# SoftRoboticsToolKit.net
KiCad netlist of a schematic drawn in Altium Designer
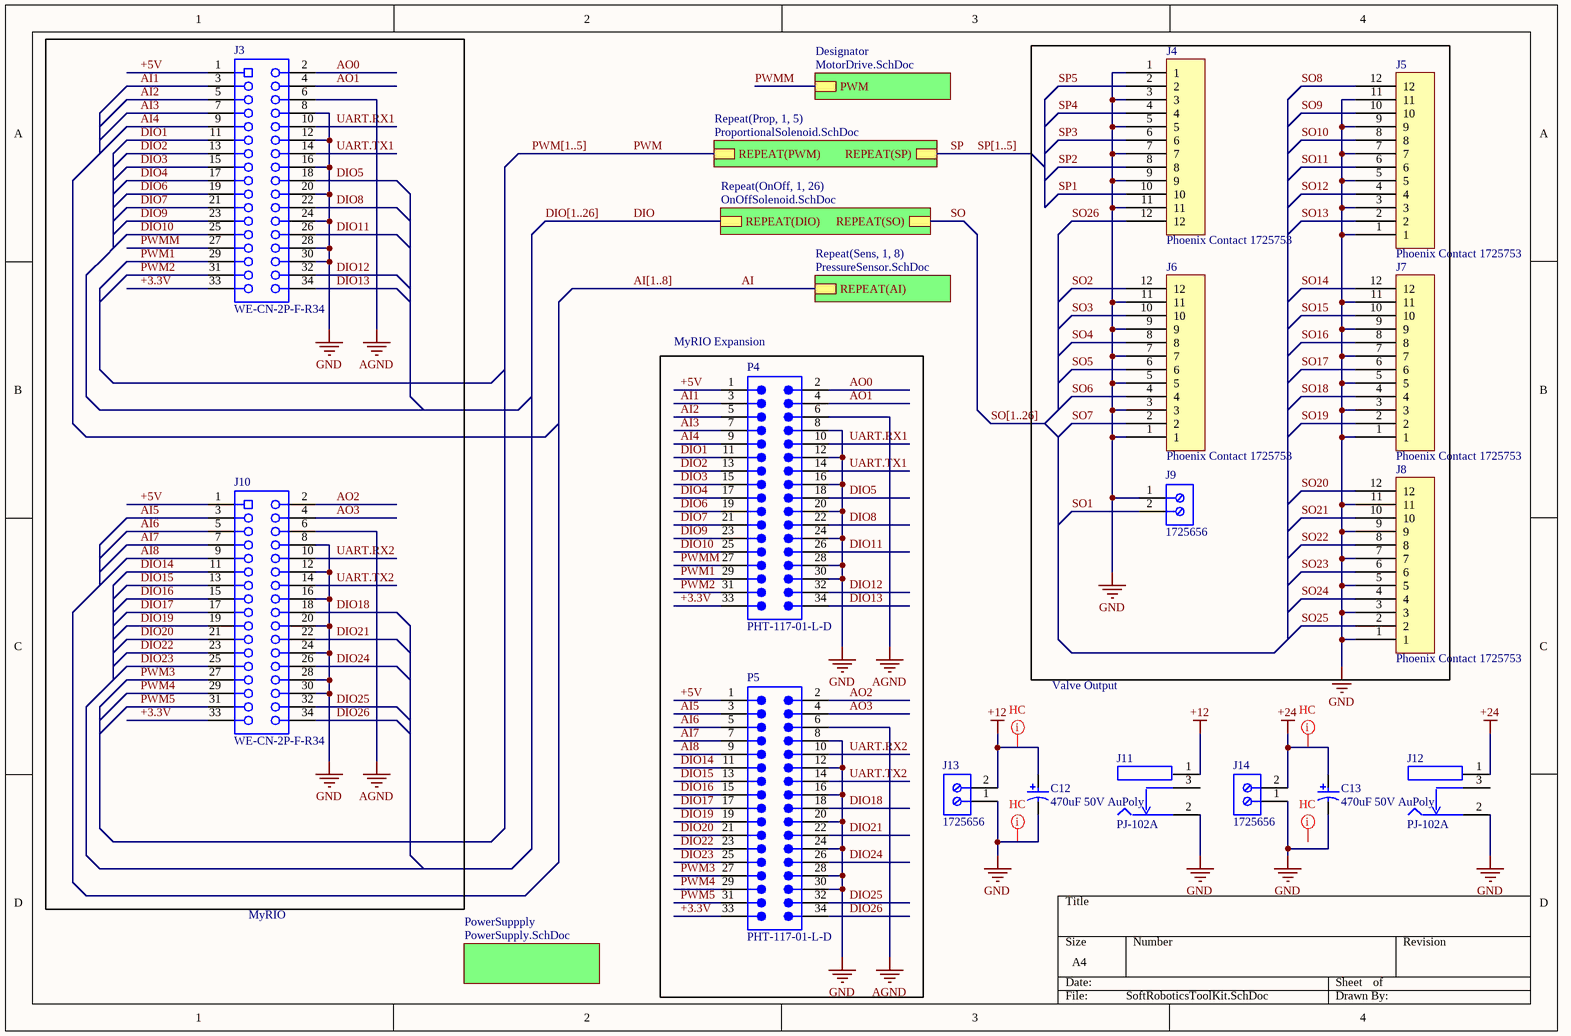
[diagram p0: SoftRoboticsToolKit.SchDoc]

(export (version "E")
  (design (tool "Eeschema 10.0.6"))
  (components
    (comp (ref "C12")
      (value "470uF 50V AuPoly")
      (footprint "CAPAE137130X163M")
      (fields (field (name "VOLTAGE") "25VDC") (field (name "MANUFACTURER") "AVX"))
      (libsource (lib "Schlib1") (part "C-Poly"))
    )
    (comp (ref "C13")
      (value "470uF 50V AuPoly")
      (footprint "CAPAE137130X163M")
      (fields (field (name "VOLTAGE") "25VDC") (field (name "MANUFACTURER") "AVX"))
      (libsource (lib "Schlib1") (part "C-Poly"))
    )
    (comp (ref "J3")
      (value "WE-CN-2P-F-R34")
      (footprint "613034243121")
      (libsource (lib "Schlib1") (part "WE-CN-2P-F-R34"))
    )
    (comp (ref "J4")
      (value "Phoenix Contact 1725753")
      (footprint "PHOE-1725656-12")
      (libsource (lib "") (part "1725753_1"))
    )
    (comp (ref "J5")
      (value "Phoenix Contact 1725753")
      (footprint "PHOE-1725656-12")
      (libsource (lib "Schlib1") (part "1725753"))
    )
    (comp (ref "J6")
      (value "Phoenix Contact 1725753")
      (footprint "PHOE-1725656-12")
      (libsource (lib "Schlib1") (part "1725753"))
    )
    (comp (ref "J7")
      (value "Phoenix Contact 1725753")
      (footprint "PHOE-1725656-12")
      (libsource (lib "Schlib1") (part "1725753"))
    )
    (comp (ref "J8")
      (value "Phoenix Contact 1725753")
      (footprint "PHOE-1725656-12")
      (libsource (lib "Schlib1") (part "1725753"))
    )
    (comp (ref "J9")
      (value "1725656")
      (footprint "PHOE-1725656-2")
      (description "Male Header, Pitch 2.54 mm, 1 x 2 Position, Height 9 mm, Tail Length 3.5 mm")
      (fields (field (name "MANUFACTURER") "Phoenix Contact"))
      (libsource (lib "Altium Content Vault") (part "CN-1P-F-TB2"))
    )
    (comp (ref "J10")
      (value "WE-CN-2P-F-R34")
      (footprint "613034243121")
      (libsource (lib "Schlib1") (part "WE-CN-2P-F-R34"))
    )
    (comp (ref "J11")
      (value "PJ-102A")
      (footprint "FP-PJ-102A-MFG")
      (description "CONN PWR JACK 2X5.5MM SOLDER")
      (fields (field (name "MANUFACTURER") "CUI") (field (name "VOLTAGE") "24V"))
      (libsource (lib "Altium Content Vault") (part "0685d7ee7311ef3291d1b1b03391b7d"))
    )
    (comp (ref "J12")
      (value "PJ-102A")
      (footprint "FP-PJ-102A-MFG")
      (description "CONN PWR JACK 2X5.5MM SOLDER")
      (fields (field (name "MANUFACTURER") "CUI") (field (name "VOLTAGE") "24V"))
      (libsource (lib "Altium Content Vault") (part "0685d7ee7311ef3291d1b1b03391b7d"))
    )
    (comp (ref "J13")
      (value "1725656")
      (footprint "PHOE-1725656-2")
      (description "Male Header, Pitch 2.54 mm, 1 x 2 Position, Height 9 mm, Tail Length 3.5 mm")
      (fields (field (name "MANUFACTURER") "Phoenix Contact"))
      (libsource (lib "Altium Content Vault") (part "CN-1P-F-TB2"))
    )
    (comp (ref "J14")
      (value "1725656")
      (footprint "PHOE-1725656-2")
      (description "Male Header, Pitch 2.54 mm, 1 x 2 Position, Height 9 mm, Tail Length 3.5 mm")
      (fields (field (name "MANUFACTURER") "Phoenix Contact"))
      (libsource (lib "Altium Content Vault") (part "CN-1P-F-TB2"))
    )
    (comp (ref "P4")
      (value "PHT-117-01-L-D")
      (footprint "PHT-117-01-L-D")
      (libsource (lib "Schlib1") (part "PHT-117-01-L-D"))
    )
    (comp (ref "P5")
      (value "PHT-117-01-L-D")
      (footprint "PHT-117-01-L-D")
      (libsource (lib "Schlib1") (part "PHT-117-01-L-D"))
    )
  )
  (nets
    (net (code "1") (name "+12") (class "Default")
      (node (ref "C12") (pin "1") (pinfunction "1_1") (pintype "passive"))
      (node (ref "J11") (pin "1") (pinfunction "1_1") (pintype "passive"))
      (node (ref "J13") (pin "2") (pinfunction "2_2") (pintype "passive"))
    )
    (net (code "2") (name "+24") (class "Default")
      (node (ref "C13") (pin "1") (pinfunction "1_1") (pintype "passive"))
      (node (ref "J12") (pin "1") (pinfunction "1_1") (pintype "passive"))
      (node (ref "J14") (pin "2") (pinfunction "2_2") (pintype "passive"))
    )
    (net (code "3") (name "/+3.3V") (class "Default")
      (node (ref "J10") (pin "33") (pinfunction "33_33") (pintype "passive"))
      (node (ref "J3") (pin "33") (pinfunction "33_33") (pintype "passive"))
      (node (ref "P4") (pin "33") (pinfunction "33_33") (pintype "passive"))
      (node (ref "P5") (pin "33") (pinfunction "33_33") (pintype "passive"))
    )
    (net (code "4") (name "/+5V") (class "Default")
      (node (ref "J10") (pin "1") (pinfunction "1_1") (pintype "passive"))
      (node (ref "J3") (pin "1") (pinfunction "1_1") (pintype "passive"))
      (node (ref "P4") (pin "1") (pinfunction "1_1") (pintype "passive"))
      (node (ref "P5") (pin "1") (pinfunction "1_1") (pintype "passive"))
    )
    (net (code "6") (name "/AI1") (class "Default")
      (node (ref "J3") (pin "3") (pinfunction "3_3") (pintype "passive"))
      (node (ref "P4") (pin "3") (pinfunction "3_3") (pintype "passive"))
    )
    (net (code "7") (name "/AI2") (class "Default")
      (node (ref "J3") (pin "5") (pinfunction "5_5") (pintype "passive"))
      (node (ref "P4") (pin "5") (pinfunction "5_5") (pintype "passive"))
    )
    (net (code "8") (name "/AI3") (class "Default")
      (node (ref "J3") (pin "7") (pinfunction "7_7") (pintype "passive"))
      (node (ref "P4") (pin "7") (pinfunction "7_7") (pintype "passive"))
    )
    (net (code "9") (name "/AI4") (class "Default")
      (node (ref "J3") (pin "9") (pinfunction "9_9") (pintype "passive"))
      (node (ref "P4") (pin "9") (pinfunction "9_9") (pintype "passive"))
    )
    (net (code "10") (name "/AI5") (class "Default")
      (node (ref "J10") (pin "3") (pinfunction "3_3") (pintype "passive"))
      (node (ref "P5") (pin "3") (pinfunction "3_3") (pintype "passive"))
    )
    (net (code "11") (name "/AI6") (class "Default")
      (node (ref "J10") (pin "5") (pinfunction "5_5") (pintype "passive"))
      (node (ref "P5") (pin "5") (pinfunction "5_5") (pintype "passive"))
    )
    (net (code "12") (name "/AI7") (class "Default")
      (node (ref "J10") (pin "7") (pinfunction "7_7") (pintype "passive"))
      (node (ref "P5") (pin "7") (pinfunction "7_7") (pintype "passive"))
    )
    (net (code "13") (name "/AI8") (class "Default")
      (node (ref "J10") (pin "9") (pinfunction "9_9") (pintype "passive"))
      (node (ref "P5") (pin "9") (pinfunction "9_9") (pintype "passive"))
    )
    (net (code "15") (name "/AO0") (class "Default")
      (node (ref "J3") (pin "2") (pinfunction "2_2") (pintype "passive"))
      (node (ref "P4") (pin "2") (pinfunction "2_2") (pintype "passive"))
    )
    (net (code "16") (name "/AO1") (class "Default")
      (node (ref "J3") (pin "4") (pinfunction "4_4") (pintype "passive"))
      (node (ref "P4") (pin "4") (pinfunction "4_4") (pintype "passive"))
    )
    (net (code "17") (name "/AO2") (class "Default")
      (node (ref "J10") (pin "2") (pinfunction "2_2") (pintype "passive"))
      (node (ref "P5") (pin "2") (pinfunction "2_2") (pintype "passive"))
    )
    (net (code "18") (name "/AO3") (class "Default")
      (node (ref "J10") (pin "4") (pinfunction "4_4") (pintype "passive"))
      (node (ref "P5") (pin "4") (pinfunction "4_4") (pintype "passive"))
    )
    (net (code "20") (name "/DIO1") (class "Default")
      (node (ref "J3") (pin "11") (pinfunction "11_11") (pintype "passive"))
      (node (ref "P4") (pin "11") (pinfunction "11_11") (pintype "passive"))
    )
    (net (code "21") (name "/DIO2") (class "Default")
      (node (ref "J3") (pin "13") (pinfunction "13_13") (pintype "passive"))
      (node (ref "P4") (pin "13") (pinfunction "13_13") (pintype "passive"))
    )
    (net (code "22") (name "/DIO3") (class "Default")
      (node (ref "J3") (pin "15") (pinfunction "15_15") (pintype "passive"))
      (node (ref "P4") (pin "15") (pinfunction "15_15") (pintype "passive"))
    )
    (net (code "23") (name "/DIO4") (class "Default")
      (node (ref "J3") (pin "17") (pinfunction "17_17") (pintype "passive"))
      (node (ref "P4") (pin "17") (pinfunction "17_17") (pintype "passive"))
    )
    (net (code "24") (name "/DIO5") (class "Default")
      (node (ref "J3") (pin "18") (pinfunction "18_18") (pintype "passive"))
      (node (ref "P4") (pin "18") (pinfunction "18_18") (pintype "passive"))
    )
    (net (code "25") (name "/DIO6") (class "Default")
      (node (ref "J3") (pin "19") (pinfunction "19_19") (pintype "passive"))
      (node (ref "P4") (pin "19") (pinfunction "19_19") (pintype "passive"))
    )
    (net (code "26") (name "/DIO7") (class "Default")
      (node (ref "J3") (pin "21") (pinfunction "21_21") (pintype "passive"))
      (node (ref "P4") (pin "21") (pinfunction "21_21") (pintype "passive"))
    )
    (net (code "27") (name "/DIO8") (class "Default")
      (node (ref "J3") (pin "22") (pinfunction "22_22") (pintype "passive"))
      (node (ref "P4") (pin "22") (pinfunction "22_22") (pintype "passive"))
    )
    (net (code "28") (name "/DIO9") (class "Default")
      (node (ref "J3") (pin "23") (pinfunction "23_23") (pintype "passive"))
      (node (ref "P4") (pin "23") (pinfunction "23_23") (pintype "passive"))
    )
    (net (code "29") (name "/DIO10") (class "Default")
      (node (ref "J3") (pin "25") (pinfunction "25_25") (pintype "passive"))
      (node (ref "P4") (pin "25") (pinfunction "25_25") (pintype "passive"))
    )
    (net (code "30") (name "/DIO11") (class "Default")
      (node (ref "J3") (pin "26") (pinfunction "26_26") (pintype "passive"))
      (node (ref "P4") (pin "26") (pinfunction "26_26") (pintype "passive"))
    )
    (net (code "31") (name "/DIO12") (class "Default")
      (node (ref "J3") (pin "32") (pinfunction "32_32") (pintype "passive"))
      (node (ref "P4") (pin "32") (pinfunction "32_32") (pintype "passive"))
    )
    (net (code "32") (name "/DIO13") (class "Default")
      (node (ref "J3") (pin "34") (pinfunction "34_34") (pintype "passive"))
      (node (ref "P4") (pin "34") (pinfunction "34_34") (pintype "passive"))
    )
    (net (code "33") (name "/DIO14") (class "Default")
      (node (ref "J10") (pin "11") (pinfunction "11_11") (pintype "passive"))
      (node (ref "P5") (pin "11") (pinfunction "11_11") (pintype "passive"))
    )
    (net (code "34") (name "/DIO15") (class "Default")
      (node (ref "J10") (pin "13") (pinfunction "13_13") (pintype "passive"))
      (node (ref "P5") (pin "13") (pinfunction "13_13") (pintype "passive"))
    )
    (net (code "35") (name "/DIO16") (class "Default")
      (node (ref "J10") (pin "15") (pinfunction "15_15") (pintype "passive"))
      (node (ref "P5") (pin "15") (pinfunction "15_15") (pintype "passive"))
    )
    (net (code "36") (name "/DIO17") (class "Default")
      (node (ref "J10") (pin "17") (pinfunction "17_17") (pintype "passive"))
      (node (ref "P5") (pin "17") (pinfunction "17_17") (pintype "passive"))
    )
    (net (code "37") (name "/DIO18") (class "Default")
      (node (ref "J10") (pin "18") (pinfunction "18_18") (pintype "passive"))
      (node (ref "P5") (pin "18") (pinfunction "18_18") (pintype "passive"))
    )
    (net (code "38") (name "/DIO19") (class "Default")
      (node (ref "J10") (pin "19") (pinfunction "19_19") (pintype "passive"))
      (node (ref "P5") (pin "19") (pinfunction "19_19") (pintype "passive"))
    )
    (net (code "39") (name "/DIO20") (class "Default")
      (node (ref "J10") (pin "21") (pinfunction "21_21") (pintype "passive"))
      (node (ref "P5") (pin "21") (pinfunction "21_21") (pintype "passive"))
    )
    (net (code "40") (name "/DIO21") (class "Default")
      (node (ref "J10") (pin "22") (pinfunction "22_22") (pintype "passive"))
      (node (ref "P5") (pin "22") (pinfunction "22_22") (pintype "passive"))
    )
    (net (code "41") (name "/DIO22") (class "Default")
      (node (ref "J10") (pin "23") (pinfunction "23_23") (pintype "passive"))
      (node (ref "P5") (pin "23") (pinfunction "23_23") (pintype "passive"))
    )
    (net (code "42") (name "/DIO23") (class "Default")
      (node (ref "J10") (pin "25") (pinfunction "25_25") (pintype "passive"))
      (node (ref "P5") (pin "25") (pinfunction "25_25") (pintype "passive"))
    )
    (net (code "43") (name "/DIO24") (class "Default")
      (node (ref "J10") (pin "26") (pinfunction "26_26") (pintype "passive"))
      (node (ref "P5") (pin "26") (pinfunction "26_26") (pintype "passive"))
    )
    (net (code "44") (name "/DIO25") (class "Default")
      (node (ref "J10") (pin "32") (pinfunction "32_32") (pintype "passive"))
      (node (ref "P5") (pin "32") (pinfunction "32_32") (pintype "passive"))
    )
    (net (code "45") (name "/DIO26") (class "Default")
      (node (ref "J10") (pin "34") (pinfunction "34_34") (pintype "passive"))
      (node (ref "P5") (pin "34") (pinfunction "34_34") (pintype "passive"))
    )
    (net (code "48") (name "/PWM1") (class "Default")
      (node (ref "J3") (pin "29") (pinfunction "29_29") (pintype "passive"))
      (node (ref "P4") (pin "29") (pinfunction "29_29") (pintype "passive"))
    )
    (net (code "49") (name "/PWM2") (class "Default")
      (node (ref "J3") (pin "31") (pinfunction "31_31") (pintype "passive"))
      (node (ref "P4") (pin "31") (pinfunction "31_31") (pintype "passive"))
    )
    (net (code "50") (name "/PWM3") (class "Default")
      (node (ref "J10") (pin "27") (pinfunction "27_27") (pintype "passive"))
      (node (ref "P5") (pin "27") (pinfunction "27_27") (pintype "passive"))
    )
    (net (code "51") (name "/PWM4") (class "Default")
      (node (ref "J10") (pin "29") (pinfunction "29_29") (pintype "passive"))
      (node (ref "P5") (pin "29") (pinfunction "29_29") (pintype "passive"))
    )
    (net (code "52") (name "/PWM5") (class "Default")
      (node (ref "J10") (pin "31") (pinfunction "31_31") (pintype "passive"))
      (node (ref "P5") (pin "31") (pinfunction "31_31") (pintype "passive"))
    )
    (net (code "53") (name "/PWMM") (class "Default")
      (node (ref "J3") (pin "27") (pinfunction "27_27") (pintype "passive"))
      (node (ref "P4") (pin "27") (pinfunction "27_27") (pintype "passive"))
    )
    (net (code "56") (name "/SO1") (class "Default")
      (node (ref "J9") (pin "2") (pinfunction "2_2") (pintype "passive"))
    )
    (net (code "57") (name "/SO2") (class "Default")
      (node (ref "J6") (pin "12") (pinfunction "12_12") (pintype "passive"))
    )
    (net (code "58") (name "/SO3") (class "Default")
      (node (ref "J6") (pin "10") (pinfunction "10_10") (pintype "passive"))
    )
    (net (code "59") (name "/SO4") (class "Default")
      (node (ref "J6") (pin "8") (pinfunction "8_8") (pintype "passive"))
    )
    (net (code "60") (name "/SO5") (class "Default")
      (node (ref "J6") (pin "6") (pinfunction "6_6") (pintype "passive"))
    )
    (net (code "61") (name "/SO6") (class "Default")
      (node (ref "J6") (pin "4") (pinfunction "4_4") (pintype "passive"))
    )
    (net (code "62") (name "/SO7") (class "Default")
      (node (ref "J6") (pin "2") (pinfunction "2_2") (pintype "passive"))
    )
    (net (code "63") (name "/SO8") (class "Default")
      (node (ref "J5") (pin "12") (pinfunction "12_12") (pintype "passive"))
    )
    (net (code "64") (name "/SO9") (class "Default")
      (node (ref "J5") (pin "10") (pinfunction "10_10") (pintype "passive"))
    )
    (net (code "65") (name "/SO10") (class "Default")
      (node (ref "J5") (pin "8") (pinfunction "8_8") (pintype "passive"))
    )
    (net (code "66") (name "/SO11") (class "Default")
      (node (ref "J5") (pin "6") (pinfunction "6_6") (pintype "passive"))
    )
    (net (code "67") (name "/SO12") (class "Default")
      (node (ref "J5") (pin "4") (pinfunction "4_4") (pintype "passive"))
    )
    (net (code "68") (name "/SO13") (class "Default")
      (node (ref "J5") (pin "2") (pinfunction "2_2") (pintype "passive"))
    )
    (net (code "69") (name "/SO14") (class "Default")
      (node (ref "J7") (pin "12") (pinfunction "12_12") (pintype "passive"))
    )
    (net (code "70") (name "/SO15") (class "Default")
      (node (ref "J7") (pin "10") (pinfunction "10_10") (pintype "passive"))
    )
    (net (code "71") (name "/SO16") (class "Default")
      (node (ref "J7") (pin "8") (pinfunction "8_8") (pintype "passive"))
    )
    (net (code "72") (name "/SO17") (class "Default")
      (node (ref "J7") (pin "6") (pinfunction "6_6") (pintype "passive"))
    )
    (net (code "73") (name "/SO18") (class "Default")
      (node (ref "J7") (pin "4") (pinfunction "4_4") (pintype "passive"))
    )
    (net (code "74") (name "/SO19") (class "Default")
      (node (ref "J7") (pin "2") (pinfunction "2_2") (pintype "passive"))
    )
    (net (code "75") (name "/SO20") (class "Default")
      (node (ref "J8") (pin "12") (pinfunction "12_12") (pintype "passive"))
    )
    (net (code "76") (name "/SO21") (class "Default")
      (node (ref "J8") (pin "10") (pinfunction "10_10") (pintype "passive"))
    )
    (net (code "77") (name "/SO22") (class "Default")
      (node (ref "J8") (pin "8") (pinfunction "8_8") (pintype "passive"))
    )
    (net (code "78") (name "/SO23") (class "Default")
      (node (ref "J8") (pin "6") (pinfunction "6_6") (pintype "passive"))
    )
    (net (code "79") (name "/SO24") (class "Default")
      (node (ref "J8") (pin "4") (pinfunction "4_4") (pintype "passive"))
    )
    (net (code "80") (name "/SO25") (class "Default")
      (node (ref "J8") (pin "2") (pinfunction "2_2") (pintype "passive"))
    )
    (net (code "81") (name "/SO26") (class "Default")
      (node (ref "J4") (pin "12") (pinfunction "12_12") (pintype "passive"))
    )
    (net (code "84") (name "/SP1") (class "Default")
      (node (ref "J4") (pin "10") (pinfunction "10_10") (pintype "passive"))
    )
    (net (code "85") (name "/SP2") (class "Default")
      (node (ref "J4") (pin "8") (pinfunction "8_8") (pintype "passive"))
    )
    (net (code "86") (name "/SP3") (class "Default")
      (node (ref "J4") (pin "6") (pinfunction "6_6") (pintype "passive"))
    )
    (net (code "87") (name "/SP4") (class "Default")
      (node (ref "J4") (pin "4") (pinfunction "4_4") (pintype "passive"))
    )
    (net (code "88") (name "/SP5") (class "Default")
      (node (ref "J4") (pin "2") (pinfunction "2_2") (pintype "passive"))
    )
    (net (code "90") (name "/UART.RX1") (class "Default")
      (node (ref "J3") (pin "10") (pinfunction "10_10") (pintype "passive"))
      (node (ref "P4") (pin "10") (pinfunction "10_10") (pintype "passive"))
    )
    (net (code "91") (name "/UART.RX2") (class "Default")
      (node (ref "J10") (pin "10") (pinfunction "10_10") (pintype "passive"))
      (node (ref "P5") (pin "10") (pinfunction "10_10") (pintype "passive"))
    )
    (net (code "92") (name "/UART.TX1") (class "Default")
      (node (ref "J3") (pin "14") (pinfunction "14_14") (pintype "passive"))
      (node (ref "P4") (pin "14") (pinfunction "14_14") (pintype "passive"))
    )
    (net (code "93") (name "/UART.TX2") (class "Default")
      (node (ref "J10") (pin "14") (pinfunction "14_14") (pintype "passive"))
      (node (ref "P5") (pin "14") (pinfunction "14_14") (pintype "passive"))
    )
    (net (code "94") (name "AGND") (class "Default")
      (node (ref "J10") (pin "6") (pinfunction "6_6") (pintype "passive"))
      (node (ref "J3") (pin "6") (pinfunction "6_6") (pintype "passive"))
      (node (ref "P4") (pin "6") (pinfunction "6_6") (pintype "passive"))
      (node (ref "P5") (pin "6") (pinfunction "6_6") (pintype "passive"))
    )
    (net (code "95") (name "GND") (class "Default")
      (node (ref "C12") (pin "2") (pinfunction "2_2") (pintype "passive"))
      (node (ref "C13") (pin "2") (pinfunction "2_2") (pintype "passive"))
      (node (ref "J10") (pin "12") (pinfunction "12_12") (pintype "passive"))
      (node (ref "J10") (pin "16") (pinfunction "16_16") (pintype "passive"))
      (node (ref "J10") (pin "20") (pinfunction "20_20") (pintype "passive"))
      (node (ref "J10") (pin "24") (pinfunction "24_24") (pintype "passive"))
      (node (ref "J10") (pin "28") (pinfunction "28_28") (pintype "passive"))
      (node (ref "J10") (pin "30") (pinfunction "30_30") (pintype "passive"))
      (node (ref "J10") (pin "8") (pinfunction "8_8") (pintype "passive"))
      (node (ref "J11") (pin "2") (pinfunction "2_2") (pintype "passive"))
      (node (ref "J12") (pin "2") (pinfunction "2_2") (pintype "passive"))
      (node (ref "J13") (pin "1") (pinfunction "1_1") (pintype "passive"))
      (node (ref "J14") (pin "1") (pinfunction "1_1") (pintype "passive"))
      (node (ref "J3") (pin "12") (pinfunction "12_12") (pintype "passive"))
      (node (ref "J3") (pin "16") (pinfunction "16_16") (pintype "passive"))
      (node (ref "J3") (pin "20") (pinfunction "20_20") (pintype "passive"))
      (node (ref "J3") (pin "24") (pinfunction "24_24") (pintype "passive"))
      (node (ref "J3") (pin "28") (pinfunction "28_28") (pintype "passive"))
      (node (ref "J3") (pin "30") (pinfunction "30_30") (pintype "passive"))
      (node (ref "J3") (pin "8") (pinfunction "8_8") (pintype "passive"))
      (node (ref "J4") (pin "1") (pinfunction "1_1") (pintype "passive"))
      (node (ref "J4") (pin "11") (pinfunction "11_11") (pintype "passive"))
      (node (ref "J4") (pin "3") (pinfunction "3_3") (pintype "passive"))
      (node (ref "J4") (pin "5") (pinfunction "5_5") (pintype "passive"))
      (node (ref "J4") (pin "7") (pinfunction "7_7") (pintype "passive"))
      (node (ref "J4") (pin "9") (pinfunction "9_9") (pintype "passive"))
      (node (ref "J5") (pin "1") (pinfunction "1_1") (pintype "passive"))
      (node (ref "J5") (pin "11") (pinfunction "11_11") (pintype "passive"))
      (node (ref "J5") (pin "3") (pinfunction "3_3") (pintype "passive"))
      (node (ref "J5") (pin "5") (pinfunction "5_5") (pintype "passive"))
      (node (ref "J5") (pin "7") (pinfunction "7_7") (pintype "passive"))
      (node (ref "J5") (pin "9") (pinfunction "9_9") (pintype "passive"))
      (node (ref "J6") (pin "1") (pinfunction "1_1") (pintype "passive"))
      (node (ref "J6") (pin "11") (pinfunction "11_11") (pintype "passive"))
      (node (ref "J6") (pin "3") (pinfunction "3_3") (pintype "passive"))
      (node (ref "J6") (pin "5") (pinfunction "5_5") (pintype "passive"))
      (node (ref "J6") (pin "7") (pinfunction "7_7") (pintype "passive"))
      (node (ref "J6") (pin "9") (pinfunction "9_9") (pintype "passive"))
      (node (ref "J7") (pin "1") (pinfunction "1_1") (pintype "passive"))
      (node (ref "J7") (pin "11") (pinfunction "11_11") (pintype "passive"))
      (node (ref "J7") (pin "3") (pinfunction "3_3") (pintype "passive"))
      (node (ref "J7") (pin "5") (pinfunction "5_5") (pintype "passive"))
      (node (ref "J7") (pin "7") (pinfunction "7_7") (pintype "passive"))
      (node (ref "J7") (pin "9") (pinfunction "9_9") (pintype "passive"))
      (node (ref "J8") (pin "1") (pinfunction "1_1") (pintype "passive"))
      (node (ref "J8") (pin "11") (pinfunction "11_11") (pintype "passive"))
      (node (ref "J8") (pin "3") (pinfunction "3_3") (pintype "passive"))
      (node (ref "J8") (pin "5") (pinfunction "5_5") (pintype "passive"))
      (node (ref "J8") (pin "7") (pinfunction "7_7") (pintype "passive"))
      (node (ref "J8") (pin "9") (pinfunction "9_9") (pintype "passive"))
      (node (ref "J9") (pin "1") (pinfunction "1_1") (pintype "passive"))
      (node (ref "P4") (pin "12") (pinfunction "12_12") (pintype "passive"))
      (node (ref "P4") (pin "16") (pinfunction "16_16") (pintype "passive"))
      (node (ref "P4") (pin "20") (pinfunction "20_20") (pintype "passive"))
      (node (ref "P4") (pin "24") (pinfunction "24_24") (pintype "passive"))
      (node (ref "P4") (pin "28") (pinfunction "28_28") (pintype "passive"))
      (node (ref "P4") (pin "30") (pinfunction "30_30") (pintype "passive"))
      (node (ref "P4") (pin "8") (pinfunction "8_8") (pintype "passive"))
      (node (ref "P5") (pin "12") (pinfunction "12_12") (pintype "passive"))
      (node (ref "P5") (pin "16") (pinfunction "16_16") (pintype "passive"))
      (node (ref "P5") (pin "20") (pinfunction "20_20") (pintype "passive"))
      (node (ref "P5") (pin "24") (pinfunction "24_24") (pintype "passive"))
      (node (ref "P5") (pin "28") (pinfunction "28_28") (pintype "passive"))
      (node (ref "P5") (pin "30") (pinfunction "30_30") (pintype "passive"))
      (node (ref "P5") (pin "8") (pinfunction "8_8") (pintype "passive"))
    )
    (net (code "96") (name "unconnected-(J11-Pad3)") (class "Default")
      (node (ref "J11") (pin "3") (pinfunction "3_3") (pintype "passive"))
    )
    (net (code "97") (name "unconnected-(J12-Pad3)") (class "Default")
      (node (ref "J12") (pin "3") (pinfunction "3_3") (pintype "passive"))
    )
  )
)
